# v1_0.net
KiCad netlist of a schematic drawn in Altium Designer
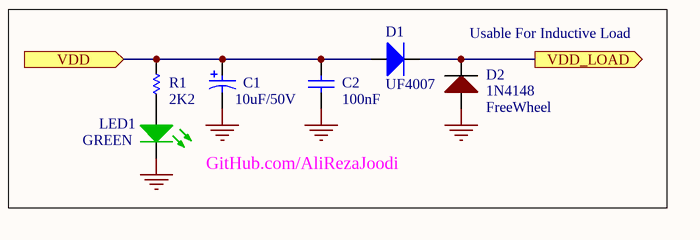
[diagram p0: v1.0.SchDoc]

(export (version "E")
  (design (tool "Eeschema 10.0.6"))
  (components
    (comp (ref "C1")
      (value "10uF/50V")
      (footprint "C_THD_EL_(P2.54-D6-H11)")
      (description "Capacitor, Electrolytic")
      (libsource (lib "Passive") (part "Capacitor_Electrolytic"))
    )
    (comp (ref "C2")
      (value "100nF")
      (footprint "C_THD_CER_(P2.54-D3.5-T1.5)")
      (description "Capacitor, Ceramic Multilayer")
      (libsource (lib "Passive") (part "Capacitor_Ceramic"))
    )
    (comp (ref "D1")
      (value "UF4007")
      (footprint "D_THD_AXIAL0.4_DO-41")
      (description "Diode,")
      (libsource (lib "Passive") (part "Diode"))
    )
    (comp (ref "D2")
      (value "1N4148")
      (footprint "D_THD_AXIAL0.3_DO-35")
      (description "Diode,")
      (libsource (lib "Passive") (part "Diode_2Form"))
    )
    (comp (ref "LED1")
      (value "GREEN")
      (footprint "LED_THD_5MM_GREEN")
      (description "LED, Green")
      (fields (field (name "MANUFACTURER") "Generic Components") (field (name "PUBLISHER") "Altium Limited"))
      (libsource (lib "Display") (part "LED_GREEN"))
    )
    (comp (ref "R1")
      (value "2K2")
      (footprint "R_THD_AXIAL0.4(1/4W)")
      (description "Resistor")
      (libsource (lib "Passive") (part "Resistor"))
    )
  )
  (nets
    (net (code "1") (name "/VDD") (class "Default")
      (node (ref "C1") (pin "1") (pinfunction "1_1") (pintype "passive"))
      (node (ref "C2") (pin "1") (pinfunction "1_1") (pintype "passive"))
      (node (ref "D1") (pin "1") (pinfunction "A_1") (pintype "passive"))
      (node (ref "R1") (pin "2") (pinfunction "2_2") (pintype "passive"))
    )
    (net (code "2") (name "/VDD_LOAD") (class "Default")
      (node (ref "D1") (pin "2") (pinfunction "K_2") (pintype "passive"))
      (node (ref "D2") (pin "2") (pinfunction "K_2") (pintype "passive"))
    )
    (net (code "3") (name "GND") (class "Default")
      (node (ref "C1") (pin "2") (pinfunction "2_2") (pintype "passive"))
      (node (ref "C2") (pin "2") (pinfunction "2_2") (pintype "passive"))
      (node (ref "D2") (pin "1") (pinfunction "A_1") (pintype "passive"))
      (node (ref "LED1") (pin "2") (pinfunction "K_2") (pintype "passive"))
    )
    (net (code "4") (name "Net-(LED1-A)") (class "Default")
      (node (ref "LED1") (pin "1") (pinfunction "A_1") (pintype "passive"))
      (node (ref "R1") (pin "1") (pinfunction "1_1") (pintype "passive"))
    )
  )
)
